# EtherNet.net
KiCad netlist of a schematic drawn in Altium Designer
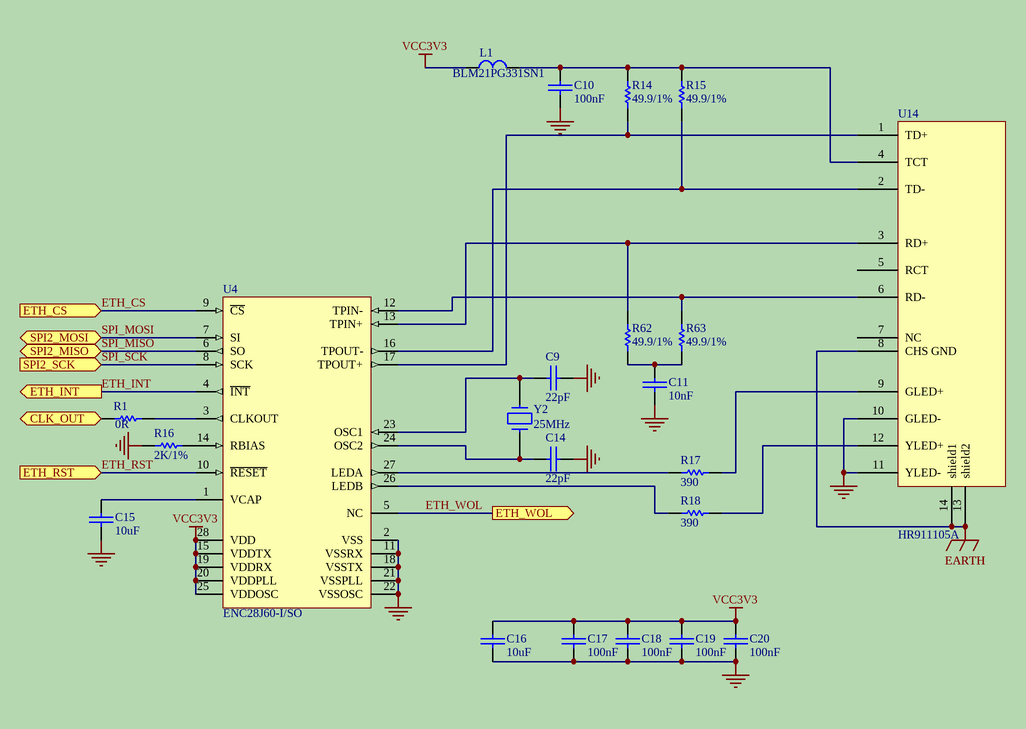
[diagram p0: EtherNet.SchDoc]

(export (version "E")
  (design (tool "Eeschema 10.0.6"))
  (components
    (comp (ref "C9")
      (value "22pF")
      (footprint "C0805")
      (description "Capacitor")
      (libsource (lib "*") (part "CAP"))
    )
    (comp (ref "C10")
      (value "100nF")
      (footprint "C0805")
      (description "Capacitor")
      (libsource (lib "*") (part "CAP"))
    )
    (comp (ref "C11")
      (value "10nF")
      (footprint "C0805")
      (description "Capacitor")
      (libsource (lib "*") (part "CAP"))
    )
    (comp (ref "C14")
      (value "22pF")
      (footprint "C0805")
      (description "Capacitor")
      (libsource (lib "*") (part "CAP"))
    )
    (comp (ref "C15")
      (value "10uF")
      (footprint "C1206")
      (description "Capacitor")
      (libsource (lib "*") (part "CAP"))
    )
    (comp (ref "C16")
      (value "10uF")
      (footprint "C1206")
      (description "Capacitor")
      (libsource (lib "*") (part "CAP"))
    )
    (comp (ref "C17")
      (value "100nF")
      (footprint "C0805")
      (description "Capacitor")
      (libsource (lib "*") (part "CAP"))
    )
    (comp (ref "C18")
      (value "100nF")
      (footprint "C0805")
      (description "Capacitor")
      (libsource (lib "*") (part "CAP"))
    )
    (comp (ref "C19")
      (value "100nF")
      (footprint "C0805")
      (description "Capacitor")
      (libsource (lib "*") (part "CAP"))
    )
    (comp (ref "C20")
      (value "100nF")
      (footprint "C0805")
      (description "Capacitor")
      (libsource (lib "*") (part "CAP"))
    )
    (comp (ref "L1") (value "BLM21PG331SN1") (footprint "L0805") (libsource (lib "Devices") (part "L1")))
    (comp (ref "R1")
      (value "0R")
      (footprint "R0805")
      (description "Resistor")
      (fields (field (name "PUBLISHER") "Altium Limited"))
      (libsource (lib "Miscellaneous Devices") (part "Res1"))
    )
    (comp (ref "R14")
      (value "49.9/1%")
      (footprint "R0805")
      (description "Resistor")
      (fields (field (name "PUBLISHER") "Altium Limited"))
      (libsource (lib "Miscellaneous Devices") (part "Res1"))
    )
    (comp (ref "R15")
      (value "49.9/1%")
      (footprint "R0805")
      (description "Resistor")
      (fields (field (name "PUBLISHER") "Altium Limited"))
      (libsource (lib "Miscellaneous Devices") (part "Res1"))
    )
    (comp (ref "R16")
      (value "2K/1%")
      (footprint "R0805")
      (description "Resistor")
      (fields (field (name "PUBLISHER") "Altium Limited"))
      (libsource (lib "Miscellaneous Devices") (part "Res1"))
    )
    (comp (ref "R17")
      (value "390")
      (footprint "R0805")
      (description "Resistor")
      (fields (field (name "PUBLISHER") "Altium Limited"))
      (libsource (lib "Miscellaneous Devices") (part "Res1"))
    )
    (comp (ref "R18")
      (value "390")
      (footprint "R0805")
      (description "Resistor")
      (fields (field (name "PUBLISHER") "Altium Limited"))
      (libsource (lib "Miscellaneous Devices") (part "Res1"))
    )
    (comp (ref "R62")
      (value "49.9/1%")
      (footprint "R0805")
      (description "Resistor")
      (fields (field (name "PUBLISHER") "Altium Limited"))
      (libsource (lib "Miscellaneous Devices") (part "Res1"))
    )
    (comp (ref "R63")
      (value "49.9/1%")
      (footprint "R0805")
      (description "Resistor")
      (fields (field (name "PUBLISHER") "Altium Limited"))
      (libsource (lib "Miscellaneous Devices") (part "Res1"))
    )
    (comp (ref "U4")
      (value "ENC28J60-I/SO")
      (footprint "SOIC-SO28_L")
      (description "Stand-Alone Ethernet Controller with SPI Interface, 28-Pin SOIC")
      (fields (field (name "PUBLISHER") "Altium Limited"))
      (libsource (lib "Microchip Interface") (part "ENC28J60/SO"))
    )
    (comp (ref "U14")
      (value "HR911105A")
      (footprint "HANRUN-A8")
      (description "RJ45 Connector with Integrated Magnetics")
      (libsource (lib "IC") (part "HR911105A"))
    )
    (comp (ref "Y2")
      (value "25MHz")
      (footprint "CRYSTAL2")
      (description "Crystal")
      (libsource (lib "*") (part "CRYSTAL"))
    )
  )
  (nets
    (net (code "1") (name "/CLK_OUT") (class "Default")
      (node (ref "R1") (pin "1") (pinfunction "1_1") (pintype "passive"))
    )
    (net (code "2") (name "/ETH_CS") (class "Default")
      (node (ref "U4") (pin "9") (pinfunction "~{CS}_9") (pintype "input"))
    )
    (net (code "3") (name "/ETH_INT") (class "Default")
      (node (ref "U4") (pin "4") (pinfunction "~{INT}_4") (pintype "output"))
    )
    (net (code "4") (name "/ETH_RST") (class "Default")
      (node (ref "U4") (pin "10") (pinfunction "~{RESET}_10") (pintype "input"))
    )
    (net (code "5") (name "/ETH_WOL") (class "Default")
      (node (ref "U4") (pin "5") (pinfunction "NC_5") (pintype "passive"))
    )
    (net (code "6") (name "/SPI_MISO") (class "Default")
      (node (ref "U4") (pin "6") (pinfunction "SO_6") (pintype "output"))
    )
    (net (code "7") (name "/SPI_MOSI") (class "Default")
      (node (ref "U4") (pin "7") (pinfunction "SI_7") (pintype "input"))
    )
    (net (code "8") (name "/SPI_SCK") (class "Default")
      (node (ref "U4") (pin "8") (pinfunction "SCK_8") (pintype "input"))
    )
    (net (code "9") (name "EARTH") (class "Default")
      (node (ref "U14") (pin "13") (pinfunction "shield2_13") (pintype "passive"))
      (node (ref "U14") (pin "14") (pinfunction "shield1_14") (pintype "passive"))
      (node (ref "U14") (pin "8") (pinfunction "CHS_GND_8") (pintype "passive"))
    )
    (net (code "10") (name "GND") (class "Default")
      (node (ref "C10") (pin "1") (pinfunction "1_1") (pintype "passive"))
      (node (ref "C11") (pin "1") (pinfunction "1_1") (pintype "passive"))
      (node (ref "C14") (pin "2") (pinfunction "2_2") (pintype "passive"))
      (node (ref "C15") (pin "1") (pinfunction "1_1") (pintype "passive"))
      (node (ref "C16") (pin "1") (pinfunction "1_1") (pintype "passive"))
      (node (ref "C17") (pin "1") (pinfunction "1_1") (pintype "passive"))
      (node (ref "C18") (pin "1") (pinfunction "1_1") (pintype "passive"))
      (node (ref "C19") (pin "1") (pinfunction "1_1") (pintype "passive"))
      (node (ref "C20") (pin "1") (pinfunction "1_1") (pintype "passive"))
      (node (ref "C9") (pin "2") (pinfunction "2_2") (pintype "passive"))
      (node (ref "R16") (pin "1") (pinfunction "1_1") (pintype "passive"))
      (node (ref "U14") (pin "10") (pinfunction "GLED-_10") (pintype "passive"))
      (node (ref "U14") (pin "11") (pinfunction "YLED-_11") (pintype "passive"))
      (node (ref "U4") (pin "11") (pinfunction "VSSRX_11") (pintype "power_in"))
      (node (ref "U4") (pin "18") (pinfunction "VSSTX_18") (pintype "power_in"))
      (node (ref "U4") (pin "2") (pinfunction "VSS_2") (pintype "power_in"))
      (node (ref "U4") (pin "21") (pinfunction "VSSPLL_21") (pintype "power_in"))
      (node (ref "U4") (pin "22") (pinfunction "VSSOSC_22") (pintype "power_in"))
    )
    (net (code "11") (name "Net-(C11-Pad2)") (class "Default")
      (node (ref "C11") (pin "2") (pinfunction "2_2") (pintype "passive"))
      (node (ref "R62") (pin "1") (pinfunction "1_1") (pintype "passive"))
      (node (ref "R63") (pin "1") (pinfunction "1_1") (pintype "passive"))
    )
    (net (code "12") (name "Net-(U4-CLKOUT)") (class "Default")
      (node (ref "R1") (pin "2") (pinfunction "2_2") (pintype "passive"))
      (node (ref "U4") (pin "3") (pinfunction "CLKOUT_3") (pintype "output"))
    )
    (net (code "13") (name "Net-(U4-LEDA)") (class "Default")
      (node (ref "R17") (pin "2") (pinfunction "2_2") (pintype "passive"))
      (node (ref "U4") (pin "27") (pinfunction "LEDA_27") (pintype "output"))
    )
    (net (code "14") (name "Net-(U4-LEDB)") (class "Default")
      (node (ref "R18") (pin "2") (pinfunction "2_2") (pintype "passive"))
      (node (ref "U4") (pin "26") (pinfunction "LEDB_26") (pintype "output"))
    )
    (net (code "15") (name "Net-(U4-OSC1)") (class "Default")
      (node (ref "C9") (pin "1") (pinfunction "1_1") (pintype "passive"))
      (node (ref "U4") (pin "23") (pinfunction "OSC1_23") (pintype "input"))
      (node (ref "Y2") (pin "1") (pinfunction "1_1") (pintype "passive"))
    )
    (net (code "16") (name "Net-(U4-OSC2)") (class "Default")
      (node (ref "C14") (pin "1") (pinfunction "1_1") (pintype "passive"))
      (node (ref "U4") (pin "24") (pinfunction "OSC2_24") (pintype "output"))
      (node (ref "Y2") (pin "2") (pinfunction "2_2") (pintype "passive"))
    )
    (net (code "17") (name "Net-(U4-RBIAS)") (class "Default")
      (node (ref "R16") (pin "2") (pinfunction "2_2") (pintype "passive"))
      (node (ref "U4") (pin "14") (pinfunction "RBIAS_14") (pintype "input"))
    )
    (net (code "18") (name "Net-(U4-VCAP)") (class "Default")
      (node (ref "C15") (pin "2") (pinfunction "2_2") (pintype "passive"))
      (node (ref "U4") (pin "1") (pinfunction "VCAP_1") (pintype "power_in"))
    )
    (net (code "19") (name "Net-(U14-GLED+)") (class "Default")
      (node (ref "R17") (pin "1") (pinfunction "1_1") (pintype "passive"))
      (node (ref "U14") (pin "9") (pinfunction "GLED+_9") (pintype "passive"))
    )
    (net (code "20") (name "Net-(U14-RD+)") (class "Default")
      (node (ref "R62") (pin "2") (pinfunction "2_2") (pintype "passive"))
      (node (ref "U14") (pin "3") (pinfunction "RD+_3") (pintype "passive"))
      (node (ref "U4") (pin "13") (pinfunction "TPIN+_13") (pintype "input"))
    )
    (net (code "21") (name "Net-(U14-RD-)") (class "Default")
      (node (ref "R63") (pin "2") (pinfunction "2_2") (pintype "passive"))
      (node (ref "U14") (pin "6") (pinfunction "RD-_6") (pintype "passive"))
      (node (ref "U4") (pin "12") (pinfunction "TPIN-_12") (pintype "input"))
    )
    (net (code "22") (name "Net-(U14-TCT)") (class "Default")
      (node (ref "C10") (pin "2") (pinfunction "2_2") (pintype "passive"))
      (node (ref "L1") (pin "2") (pinfunction "2_2") (pintype "passive"))
      (node (ref "R14") (pin "1") (pinfunction "1_1") (pintype "passive"))
      (node (ref "R15") (pin "1") (pinfunction "1_1") (pintype "passive"))
      (node (ref "U14") (pin "4") (pinfunction "TCT_4") (pintype "passive"))
    )
    (net (code "23") (name "Net-(U14-TD+)") (class "Default")
      (node (ref "R14") (pin "2") (pinfunction "2_2") (pintype "passive"))
      (node (ref "U14") (pin "1") (pinfunction "TD+_1") (pintype "passive"))
      (node (ref "U4") (pin "17") (pinfunction "TPOUT+_17") (pintype "output"))
    )
    (net (code "24") (name "Net-(U14-TD-)") (class "Default")
      (node (ref "R15") (pin "2") (pinfunction "2_2") (pintype "passive"))
      (node (ref "U14") (pin "2") (pinfunction "TD-_2") (pintype "passive"))
      (node (ref "U4") (pin "16") (pinfunction "TPOUT-_16") (pintype "output"))
    )
    (net (code "25") (name "Net-(U14-YLED+)") (class "Default")
      (node (ref "R18") (pin "1") (pinfunction "1_1") (pintype "passive"))
      (node (ref "U14") (pin "12") (pinfunction "YLED+_12") (pintype "passive"))
    )
    (net (code "26") (name "VCC3V3") (class "Default")
      (node (ref "C16") (pin "2") (pinfunction "2_2") (pintype "passive"))
      (node (ref "C17") (pin "2") (pinfunction "2_2") (pintype "passive"))
      (node (ref "C18") (pin "2") (pinfunction "2_2") (pintype "passive"))
      (node (ref "C19") (pin "2") (pinfunction "2_2") (pintype "passive"))
      (node (ref "C20") (pin "2") (pinfunction "2_2") (pintype "passive"))
      (node (ref "L1") (pin "1") (pinfunction "1_1") (pintype "passive"))
      (node (ref "U4") (pin "15") (pinfunction "VDDTX_15") (pintype "power_in"))
      (node (ref "U4") (pin "19") (pinfunction "VDDRX_19") (pintype "power_in"))
      (node (ref "U4") (pin "20") (pinfunction "VDDPLL_20") (pintype "power_in"))
      (node (ref "U4") (pin "25") (pinfunction "VDDOSC_25") (pintype "power_in"))
      (node (ref "U4") (pin "28") (pinfunction "VDD_28") (pintype "power_in"))
    )
    (net (code "27") (name "unconnected-(U14-NC-Pad7)") (class "Default")
      (node (ref "U14") (pin "7") (pinfunction "NC_7") (pintype "passive"))
    )
    (net (code "28") (name "unconnected-(U14-RCT-Pad5)") (class "Default")
      (node (ref "U14") (pin "5") (pinfunction "RCT_5") (pintype "passive"))
    )
  )
)
